# ETH_PCIE_PHY.net
KiCad netlist of a schematic drawn in Altium Designer
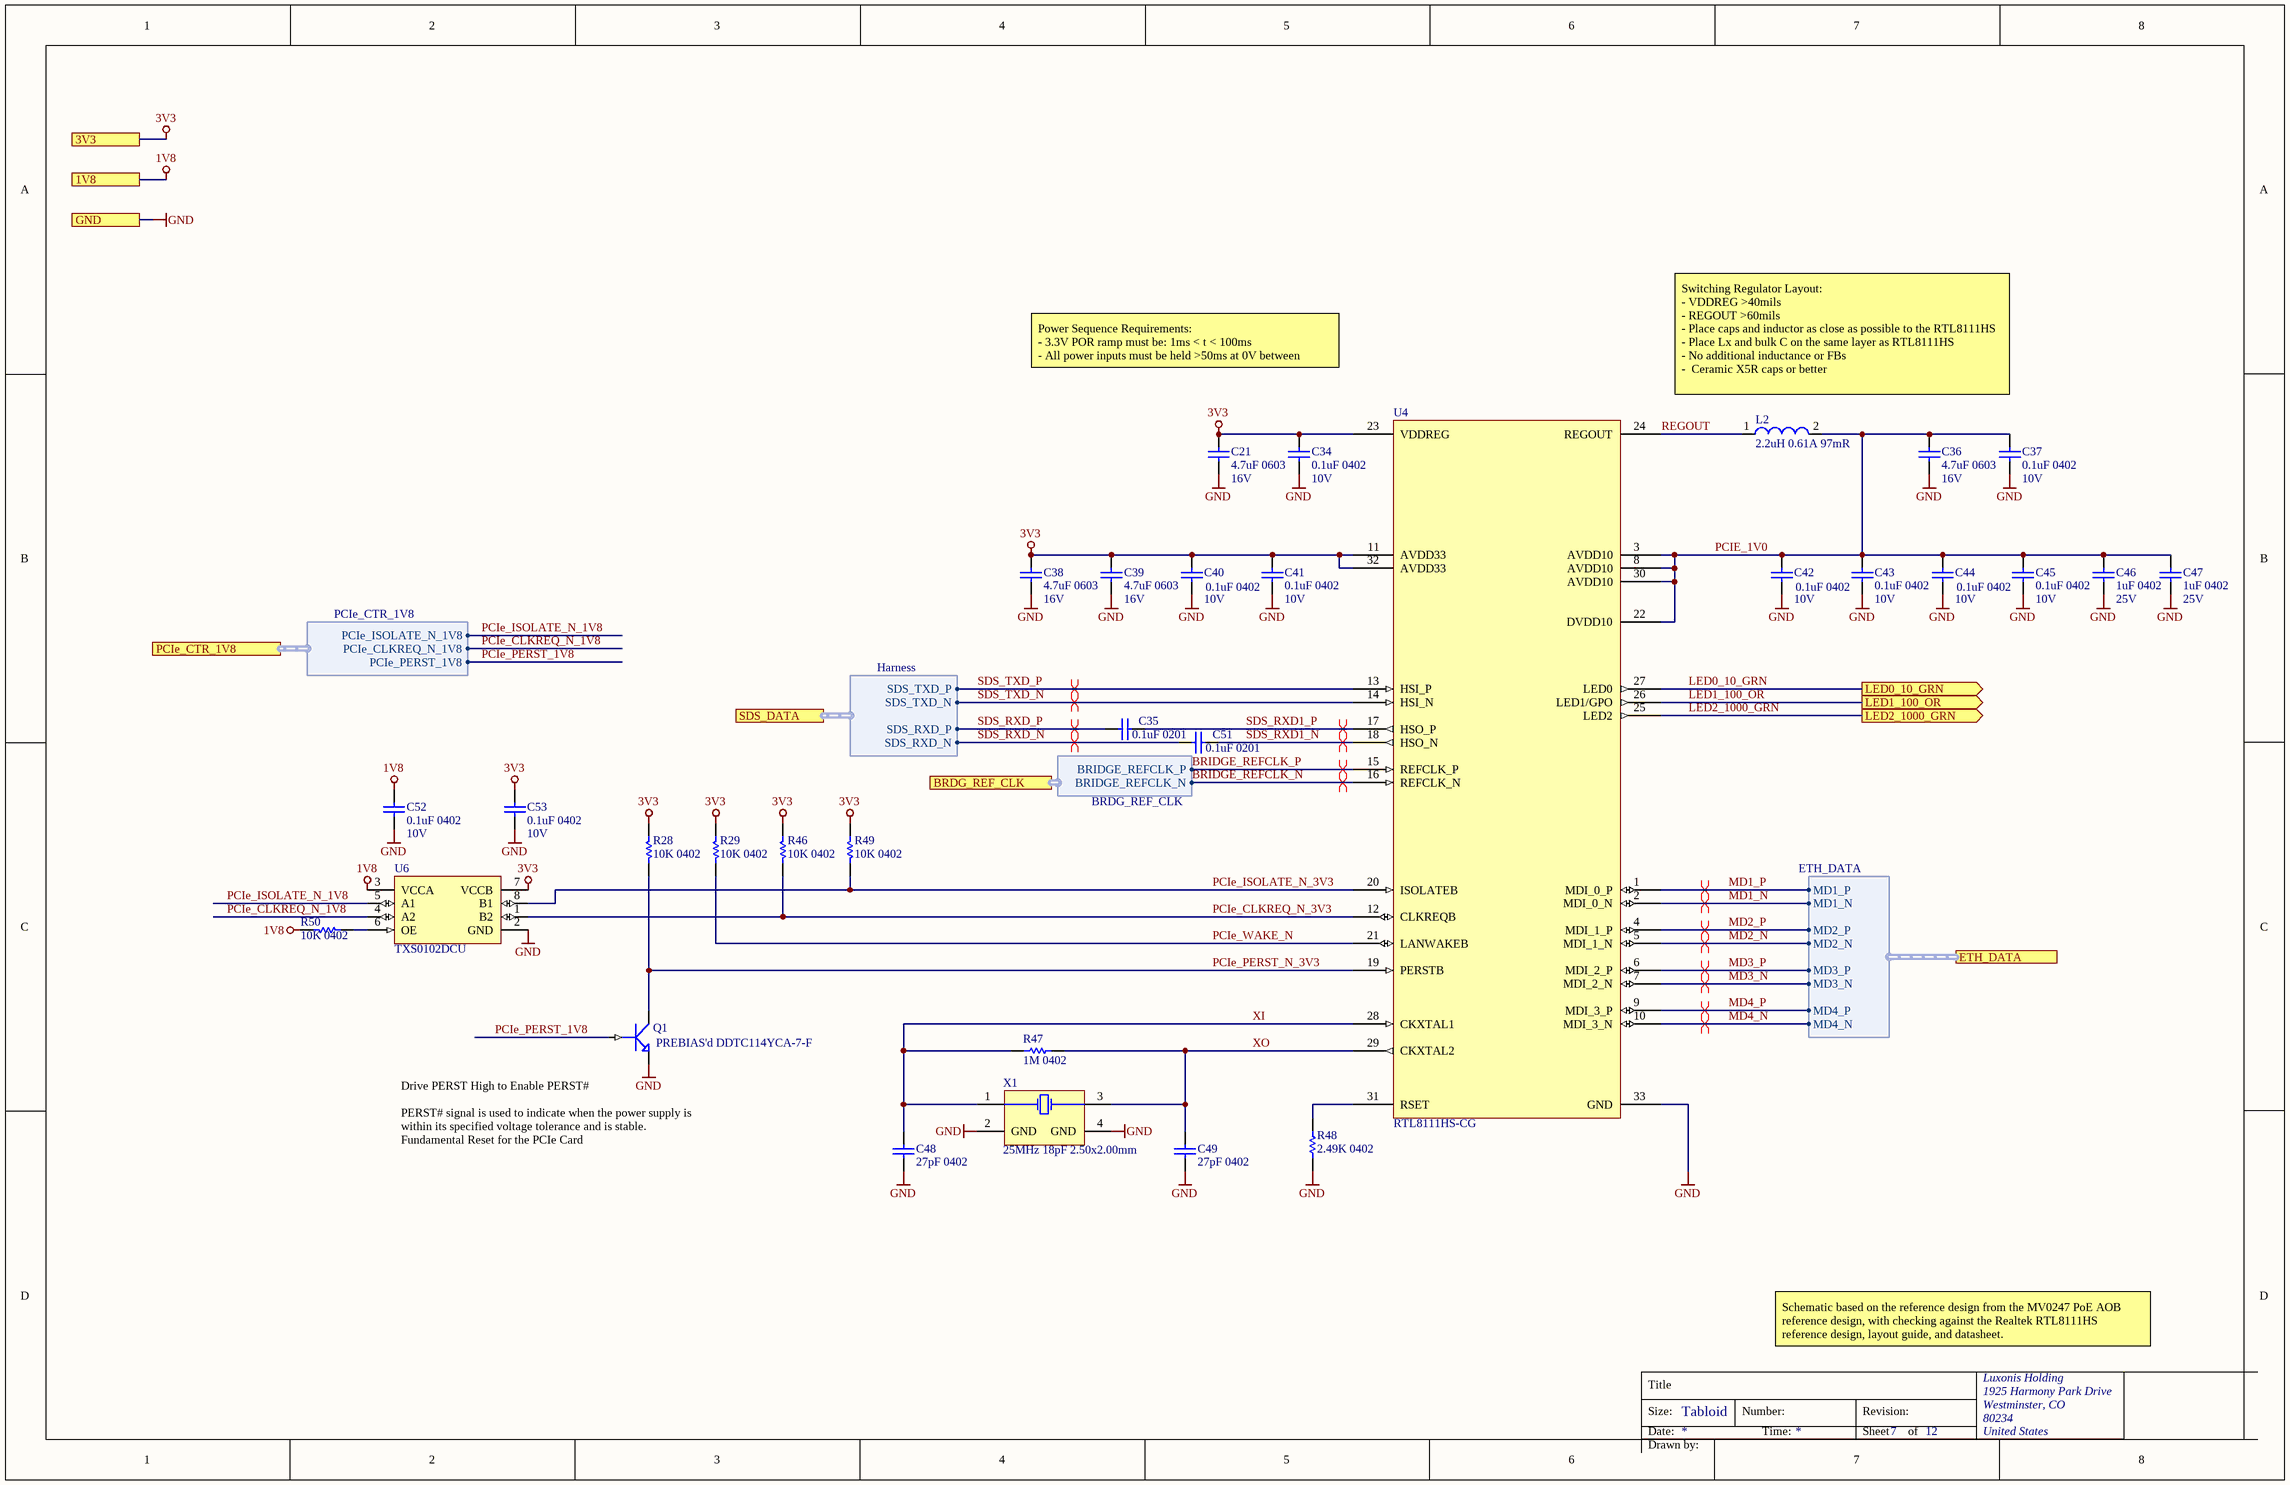
[diagram p0: ETH_PCIE_PHY.SchDoc]

(export (version "E")
  (design (tool "Eeschema 10.0.6"))
  (components
    (comp (ref "C21")
      (value "4.7uF 0603")
      (footprint "CAP_Altium_Vault_Generic:CAPC0603(1608)100_N")
      (description "CAP CER 4.7UF 16V X5R 0603 10%")
      (fields (field (name "TOLERANCE") "10%") (field (name "VOLTAGE RATING") "16V"))
      (libsource (lib "LuxonisMaster") (part "GRM188R61C475KAAJD"))
    )
    (comp (ref "C34")
      (value "0.1uF 0402")
      (footprint "CAP_Altium_Vault_Generic:CAPC0402(1005)70_N")
      (description "CAP CER 0.1UF 10V X7R 0402 5%")
      (fields (field (name "TOLERANCE") "5%") (field (name "VOLTAGE RATING") "10V"))
      (libsource (lib "LuxonisMaster") (part "GRM155R71A104JA01D"))
    )
    (comp (ref "C35")
      (value "0.1uF 0201")
      (footprint "CAP_Altium_Vault_Generic:CAPC0201(0603)33_L")
      (description "CAP CER 0.1UF 10V X5R 0201")
      (fields (field (name "TOLERANCE") "10%") (field (name "VOLTAGE") "10V"))
      (libsource (lib "LuxonisMaster") (part "GRM033R61A104KE15D"))
    )
    (comp (ref "C36")
      (value "4.7uF 0603")
      (footprint "CAP_Altium_Vault_Generic:CAPC0603(1608)100_N")
      (description "CAP CER 4.7UF 16V X5R 0603 10%")
      (fields (field (name "TOLERANCE") "10%") (field (name "VOLTAGE RATING") "16V"))
      (libsource (lib "LuxonisMaster") (part "GRM188R61C475KAAJD"))
    )
    (comp (ref "C37")
      (value "0.1uF 0402")
      (footprint "CAP_Altium_Vault_Generic:CAPC0402(1005)70_N")
      (description "CAP CER 0.1UF 10V X7R 0402 5%")
      (fields (field (name "TOLERANCE") "5%") (field (name "VOLTAGE RATING") "10V"))
      (libsource (lib "LuxonisMaster") (part "GRM155R71A104JA01D"))
    )
    (comp (ref "C38")
      (value "4.7uF 0603")
      (footprint "CAP_Altium_Vault_Generic:CAPC0603(1608)100_N")
      (description "CAP CER 4.7UF 16V X5R 0603 10%")
      (fields (field (name "TOLERANCE") "10%") (field (name "VOLTAGE RATING") "16V"))
      (libsource (lib "LuxonisMaster") (part "GRM188R61C475KAAJD"))
    )
    (comp (ref "C39")
      (value "4.7uF 0603")
      (footprint "CAP_Altium_Vault_Generic:CAPC0603(1608)100_N")
      (description "CAP CER 4.7UF 16V X5R 0603 10%")
      (fields (field (name "TOLERANCE") "10%") (field (name "VOLTAGE RATING") "16V"))
      (libsource (lib "LuxonisMaster") (part "GRM188R61C475KAAJD"))
    )
    (comp (ref "C40")
      (value "0.1uF 0402")
      (footprint "CAP_Altium_Vault_Generic:CAPC0402(1005)70_N")
      (description "CAP CER 0.1UF 10V X7R 0402 5%")
      (fields (field (name "TOLERANCE") "5%") (field (name "VOLTAGE RATING") "10V"))
      (libsource (lib "LuxonisMaster") (part "GRM155R71A104JA01D"))
    )
    (comp (ref "C41")
      (value "0.1uF 0402")
      (footprint "CAP_Altium_Vault_Generic:CAPC0402(1005)70_N")
      (description "CAP CER 0.1UF 10V X7R 0402 5%")
      (fields (field (name "TOLERANCE") "5%") (field (name "VOLTAGE RATING") "10V"))
      (libsource (lib "LuxonisMaster") (part "GRM155R71A104JA01D"))
    )
    (comp (ref "C42")
      (value "0.1uF 0402")
      (footprint "CAP_Altium_Vault_Generic:CAPC0402(1005)70_N")
      (description "CAP CER 0.1UF 10V X7R 0402 5%")
      (fields (field (name "TOLERANCE") "5%") (field (name "VOLTAGE RATING") "10V"))
      (libsource (lib "LuxonisMaster") (part "GRM155R71A104JA01D"))
    )
    (comp (ref "C43")
      (value "0.1uF 0402")
      (footprint "CAP_Altium_Vault_Generic:CAPC0402(1005)70_N")
      (description "CAP CER 0.1UF 10V X7R 0402 5%")
      (fields (field (name "TOLERANCE") "5%") (field (name "VOLTAGE RATING") "10V"))
      (libsource (lib "LuxonisMaster") (part "GRM155R71A104JA01D"))
    )
    (comp (ref "C44")
      (value "0.1uF 0402")
      (footprint "CAP_Altium_Vault_Generic:CAPC0402(1005)70_N")
      (description "CAP CER 0.1UF 10V X7R 0402 5%")
      (fields (field (name "TOLERANCE") "5%") (field (name "VOLTAGE RATING") "10V"))
      (libsource (lib "LuxonisMaster") (part "GRM155R71A104JA01D"))
    )
    (comp (ref "C45")
      (value "0.1uF 0402")
      (footprint "CAP_Altium_Vault_Generic:CAPC0402(1005)70_N")
      (description "CAP CER 0.1UF 10V X7R 0402 5%")
      (fields (field (name "TOLERANCE") "5%") (field (name "VOLTAGE RATING") "10V"))
      (libsource (lib "LuxonisMaster") (part "GRM155R71A104JA01D"))
    )
    (comp (ref "C46")
      (value "1uF 0402")
      (footprint "CAP_Altium_Vault_Generic:CAPC0402(1005)70_N")
      (description "CAP CER 1UF 25V X5R 0402 10%")
      (fields
        (field (name "TOLERANCE") "10%")
        (field (name "VOLTAGE") "25V")
        (field (name "VOLTAGE RATING") "25V")
      )
      (libsource (lib "LuxonisMaster") (part "GRM155R61E105KA12D"))
    )
    (comp (ref "C47")
      (value "1uF 0402")
      (footprint "CAP_Altium_Vault_Generic:CAPC0402(1005)70_N")
      (description "CAP CER 1UF 25V X5R 0402 10%")
      (fields
        (field (name "TOLERANCE") "10%")
        (field (name "VOLTAGE") "25V")
        (field (name "VOLTAGE RATING") "25V")
      )
      (libsource (lib "LuxonisMaster") (part "GRM155R61E105KA12D"))
    )
    (comp (ref "C48")
      (value "27pF 0402")
      (footprint "CAP_Altium_Vault_Generic:CAPC0402(1005)60_N")
      (description "CAP CER 27PF 50V C0G/NP0 0402")
      (fields (field (name "TOLERANCE") "5%") (field (name "VOLTAGE") "50V"))
      (libsource (lib "BW2098POE") (part "C0402C270J5GACTU"))
    )
    (comp (ref "C49")
      (value "27pF 0402")
      (footprint "CAP_Altium_Vault_Generic:CAPC0402(1005)60_N")
      (description "CAP CER 27PF 50V C0G/NP0 0402")
      (fields (field (name "TOLERANCE") "5%") (field (name "VOLTAGE") "50V"))
      (libsource (lib "BW2098POE") (part "C0402C270J5GACTU"))
    )
    (comp (ref "C51")
      (value "0.1uF 0201")
      (footprint "CAP_Altium_Vault_Generic:CAPC0201(0603)33_L")
      (description "CAP CER 0.1UF 10V X5R 0201")
      (fields (field (name "TOLERANCE") "10%") (field (name "VOLTAGE") "10V"))
      (libsource (lib "LuxonisMaster") (part "GRM033R61A104KE15D"))
    )
    (comp (ref "C52")
      (value "0.1uF 0402")
      (footprint "CAP_Altium_Vault_Generic:CAPC0402(1005)70_N")
      (description "CAP CER 0.1UF 10V X7R 0402 5%")
      (fields (field (name "TOLERANCE") "5%") (field (name "VOLTAGE RATING") "10V"))
      (libsource (lib "LuxonisMaster") (part "GRM155R71A104JA01D"))
    )
    (comp (ref "C53")
      (value "0.1uF 0402")
      (footprint "CAP_Altium_Vault_Generic:CAPC0402(1005)70_N")
      (description "CAP CER 0.1UF 10V X7R 0402 5%")
      (fields (field (name "TOLERANCE") "5%") (field (name "VOLTAGE RATING") "10V"))
      (libsource (lib "LuxonisMaster") (part "GRM155R71A104JA01D"))
    )
    (comp (ref "L2")
      (value "2.2uH 0.61A 97mR")
      (footprint "BW2098POE:LQH32NH2R2J23L")
      (description "FIXED IND 2.2UH 610MA 97MOHM SMD")
      (fields (field (name "TOLERANCE") "5%"))
      (libsource (lib "BW2098POE") (part "LQH32NH2R2J23L"))
    )
    (comp (ref "Q1")
      (value "PREBIAS'd DDTC114YCA-7-F")
      (footprint "BW2098POE:DDTC114YCA-7-F")
      (description "TRANS PREBIAS NPN 200MW SOT23-3")
      (libsource (lib "BW2098POE") (part "DDTC114YCA-7-F"))
    )
    (comp (ref "R28")
      (value "10K 0402")
      (footprint "RES_Altium_Vault_Generic:RESC0402(1005)_N")
      (fields (field (name "TOLERANCE") "1%"))
      (libsource (lib "LuxonisMaster") (part "RC0402FR-1310KL"))
    )
    (comp (ref "R29")
      (value "10K 0402")
      (footprint "RES_Altium_Vault_Generic:RESC0402(1005)_N")
      (fields (field (name "TOLERANCE") "1%"))
      (libsource (lib "LuxonisMaster") (part "RC0402FR-1310KL"))
    )
    (comp (ref "R46")
      (value "10K 0402")
      (footprint "RES_Altium_Vault_Generic:RESC0402(1005)_N")
      (fields (field (name "TOLERANCE") "1%"))
      (libsource (lib "LuxonisMaster") (part "RC0402FR-1310KL"))
    )
    (comp (ref "R47")
      (value "1M 0402")
      (footprint "RES_Altium_Vault_Generic:RESC0402(1005)_N")
      (description "RES SMD 1M OHM 1% 1/16W 0402")
      (fields (field (name "TOLERANCE") "1%"))
      (libsource (lib "LuxonisMaster") (part "RC0402FR-071ML"))
    )
    (comp (ref "R48")
      (value "2.49K 0402")
      (footprint "RES_Altium_Vault_Generic:RESC0402(1005)_N")
      (description "RES SMD 2.49K OHM 1% 1/16W 0402")
      (fields (field (name "TOLERANCE") "1%"))
      (libsource (lib "BW2098POE") (part "RC0402FR-072K49L"))
    )
    (comp (ref "R49")
      (value "10K 0402")
      (footprint "RES_Altium_Vault_Generic:RESC0402(1005)_N")
      (fields (field (name "TOLERANCE") "1%"))
      (libsource (lib "LuxonisMaster") (part "RC0402FR-1310KL"))
    )
    (comp (ref "R50")
      (value "10K 0402")
      (footprint "RES_Altium_Vault_Generic:RESC0402(1005)_N")
      (fields (field (name "TOLERANCE") "1%"))
      (libsource (lib "LuxonisMaster") (part "RC0402FR-1310KL"))
    )
    (comp (ref "U4")
      (value "RTL8111HS-CG")
      (footprint "BW2098POE:RTL8111Hx-CG")
      (description "IC ETHERNET/PCIe PHY Realtek")
      (libsource (lib "BW2098POE") (part "RTL8111HS"))
    )
    (comp (ref "U6")
      (value "TXS0102DCU")
      (footprint "BW2098POE:TXS0102DCUR")
      (description "TEXAS INSTRUMENTS - TXS0102DCUR - IC, TRANSLATOR, 2 BIT, BI, US-8")
      (libsource (lib "BW2098POE") (part "TXS0102DCUR"))
    )
    (comp (ref "X1")
      (value "25MHz 18pF 2.50x2.00mm")
      (footprint "BW2098POE:ECS-250-18-36B-CKY-TR")
      (description "CRYSTAL 25.0000MHZ 18PF SMD 25MHz ±10ppm Crystal 18pF 50 Ohms 4-SMD, No Lead")
      (libsource (lib "BW2098POE") (part "ECS-250-18-36B-CKY-TR"))
    )
  )
  (nets
    (net (code "5") (name "/BRIDGE_REFCLK_N") (class "Default")
      (node (ref "U4") (pin "16") (pinfunction "REFCLK_N_16") (pintype "input"))
    )
    (net (code "6") (name "/BRIDGE_REFCLK_P") (class "Default")
      (node (ref "U4") (pin "15") (pinfunction "REFCLK_P_15") (pintype "input"))
    )
    (net (code "7") (name "/LED0_10_GRN") (class "Default")
      (node (ref "U4") (pin "27") (pinfunction "LED0_27") (pintype "output"))
    )
    (net (code "8") (name "/LED1_100_OR") (class "Default")
      (node (ref "U4") (pin "26") (pinfunction "LED1/GPO_26") (pintype "output"))
    )
    (net (code "9") (name "/LED2_1000_GRN") (class "Default")
      (node (ref "U4") (pin "25") (pinfunction "LED2_25") (pintype "output"))
    )
    (net (code "10") (name "/MD1_N") (class "Default")
      (node (ref "U4") (pin "2") (pinfunction "MDI_0_N_2") (pintype "bidirectional"))
    )
    (net (code "11") (name "/MD1_P") (class "Default")
      (node (ref "U4") (pin "1") (pinfunction "MDI_0_P_1") (pintype "bidirectional"))
    )
    (net (code "12") (name "/MD2_N") (class "Default")
      (node (ref "U4") (pin "5") (pinfunction "MDI_1_N_5") (pintype "bidirectional"))
    )
    (net (code "13") (name "/MD2_P") (class "Default")
      (node (ref "U4") (pin "4") (pinfunction "MDI_1_P_4") (pintype "bidirectional"))
    )
    (net (code "14") (name "/MD3_N") (class "Default")
      (node (ref "U4") (pin "7") (pinfunction "MDI_2_N_7") (pintype "bidirectional"))
    )
    (net (code "15") (name "/MD3_P") (class "Default")
      (node (ref "U4") (pin "6") (pinfunction "MDI_2_P_6") (pintype "bidirectional"))
    )
    (net (code "16") (name "/MD4_N") (class "Default")
      (node (ref "U4") (pin "10") (pinfunction "MDI_3_N_10") (pintype "bidirectional"))
    )
    (net (code "17") (name "/MD4_P") (class "Default")
      (node (ref "U4") (pin "9") (pinfunction "MDI_3_P_9") (pintype "bidirectional"))
    )
    (net (code "18") (name "/PCIE_1V0") (class "Default")
      (node (ref "C36") (pin "2") (pinfunction "2_2") (pintype "passive"))
      (node (ref "C37") (pin "2") (pinfunction "2_2") (pintype "passive"))
      (node (ref "C42") (pin "2") (pinfunction "2_2") (pintype "passive"))
      (node (ref "C43") (pin "2") (pinfunction "2_2") (pintype "passive"))
      (node (ref "C44") (pin "2") (pinfunction "2_2") (pintype "passive"))
      (node (ref "C45") (pin "2") (pinfunction "2_2") (pintype "passive"))
      (node (ref "C46") (pin "2") (pinfunction "2_2") (pintype "passive"))
      (node (ref "C47") (pin "2") (pinfunction "2_2") (pintype "passive"))
      (node (ref "L2") (pin "2") (pinfunction "2_2") (pintype "passive"))
      (node (ref "U4") (pin "22") (pinfunction "DVDD10_22") (pintype "passive"))
      (node (ref "U4") (pin "3") (pinfunction "AVDD10_3") (pintype "passive"))
      (node (ref "U4") (pin "30") (pinfunction "AVDD10_30") (pintype "passive"))
      (node (ref "U4") (pin "8") (pinfunction "AVDD10_8") (pintype "passive"))
    )
    (net (code "19") (name "/PCIe_CLKREQ_N_1V8") (class "Default")
      (node (ref "U6") (pin "4") (pinfunction "A2_4") (pintype "bidirectional"))
    )
    (net (code "20") (name "/PCIe_CLKREQ_N_3V3") (class "Default")
      (node (ref "R46") (pin "2") (pinfunction "2_2") (pintype "passive"))
      (node (ref "U4") (pin "12") (pinfunction "CLKREQB_12") (pintype "bidirectional"))
      (node (ref "U6") (pin "1") (pinfunction "B2_1") (pintype "bidirectional"))
    )
    (net (code "21") (name "/PCIe_ISOLATE_N_1V8") (class "Default")
      (node (ref "U6") (pin "5") (pinfunction "A1_5") (pintype "bidirectional"))
    )
    (net (code "22") (name "/PCIe_ISOLATE_N_3V3") (class "Default")
      (node (ref "R49") (pin "2") (pinfunction "2_2") (pintype "passive"))
      (node (ref "U4") (pin "20") (pinfunction "ISOLATEB_20") (pintype "input"))
      (node (ref "U6") (pin "8") (pinfunction "B1_8") (pintype "bidirectional"))
    )
    (net (code "23") (name "/PCIe_PERST_1V8") (class "Default")
      (node (ref "Q1") (pin "1") (pinfunction "B_1") (pintype "input"))
    )
    (net (code "24") (name "/PCIe_PERST_N_3V3") (class "Default")
      (node (ref "Q1") (pin "3") (pinfunction "C_3") (pintype "passive"))
      (node (ref "R28") (pin "2") (pinfunction "2_2") (pintype "passive"))
      (node (ref "U4") (pin "19") (pinfunction "PERSTB_19") (pintype "input"))
    )
    (net (code "25") (name "/PCIe_WAKE_N") (class "Default")
      (node (ref "R29") (pin "2") (pinfunction "2_2") (pintype "passive"))
      (node (ref "U4") (pin "21") (pinfunction "LANWAKEB_21") (pintype "bidirectional"))
    )
    (net (code "26") (name "/REGOUT") (class "Default")
      (node (ref "L2") (pin "1") (pinfunction "1_1") (pintype "passive"))
      (node (ref "U4") (pin "24") (pinfunction "REGOUT_24") (pintype "passive"))
    )
    (net (code "27") (name "/SDS_RXD1_N") (class "Default")
      (node (ref "C51") (pin "2") (pinfunction "2_2") (pintype "passive"))
      (node (ref "U4") (pin "18") (pinfunction "HSO_N_18") (pintype "output"))
    )
    (net (code "28") (name "/SDS_RXD1_P") (class "Default")
      (node (ref "C35") (pin "2") (pinfunction "2_2") (pintype "passive"))
      (node (ref "U4") (pin "17") (pinfunction "HSO_P_17") (pintype "output"))
    )
    (net (code "29") (name "/SDS_RXD_N") (class "Default")
      (node (ref "C51") (pin "1") (pinfunction "1_1") (pintype "passive"))
    )
    (net (code "30") (name "/SDS_RXD_P") (class "Default")
      (node (ref "C35") (pin "1") (pinfunction "1_1") (pintype "passive"))
    )
    (net (code "31") (name "/SDS_TXD_N") (class "Default")
      (node (ref "U4") (pin "14") (pinfunction "HSI_N_14") (pintype "input"))
    )
    (net (code "32") (name "/SDS_TXD_P") (class "Default")
      (node (ref "U4") (pin "13") (pinfunction "HSI_P_13") (pintype "input"))
    )
    (net (code "33") (name "/XI") (class "Default")
      (node (ref "C48") (pin "2") (pinfunction "2_2") (pintype "passive"))
      (node (ref "R47") (pin "1") (pinfunction "1_1") (pintype "passive"))
      (node (ref "U4") (pin "28") (pinfunction "CKXTAL1_28") (pintype "input"))
      (node (ref "X1") (pin "1") (pinfunction "X1_1") (pintype "passive"))
    )
    (net (code "34") (name "/XO") (class "Default")
      (node (ref "C49") (pin "2") (pinfunction "2_2") (pintype "passive"))
      (node (ref "R47") (pin "2") (pinfunction "2_2") (pintype "passive"))
      (node (ref "U4") (pin "29") (pinfunction "CKXTAL2_29") (pintype "output"))
      (node (ref "X1") (pin "3") (pinfunction "X2_3") (pintype "passive"))
    )
    (net (code "39") (name "1V8") (class "Default")
      (node (ref "C52") (pin "2") (pinfunction "2_2") (pintype "passive"))
      (node (ref "R50") (pin "2") (pinfunction "2_2") (pintype "passive"))
      (node (ref "U6") (pin "3") (pinfunction "VCCA_3") (pintype "power_in"))
    )
    (net (code "40") (name "3V3") (class "Default")
      (node (ref "C21") (pin "2") (pinfunction "2_2") (pintype "passive"))
      (node (ref "C34") (pin "2") (pinfunction "2_2") (pintype "passive"))
      (node (ref "C38") (pin "2") (pinfunction "2_2") (pintype "passive"))
      (node (ref "C39") (pin "2") (pinfunction "2_2") (pintype "passive"))
      (node (ref "C40") (pin "2") (pinfunction "2_2") (pintype "passive"))
      (node (ref "C41") (pin "2") (pinfunction "2_2") (pintype "passive"))
      (node (ref "C53") (pin "2") (pinfunction "2_2") (pintype "passive"))
      (node (ref "R28") (pin "1") (pinfunction "1_1") (pintype "passive"))
      (node (ref "R29") (pin "1") (pinfunction "1_1") (pintype "passive"))
      (node (ref "R46") (pin "1") (pinfunction "1_1") (pintype "passive"))
      (node (ref "R49") (pin "1") (pinfunction "1_1") (pintype "passive"))
      (node (ref "U4") (pin "11") (pinfunction "AVDD33_11") (pintype "passive"))
      (node (ref "U4") (pin "23") (pinfunction "VDDREG_23") (pintype "passive"))
      (node (ref "U4") (pin "32") (pinfunction "AVDD33_32") (pintype "passive"))
      (node (ref "U6") (pin "7") (pinfunction "VCCB_7") (pintype "power_in"))
    )
    (net (code "41") (name "GND") (class "Default")
      (node (ref "C21") (pin "1") (pinfunction "1_1") (pintype "passive"))
      (node (ref "C34") (pin "1") (pinfunction "1_1") (pintype "passive"))
      (node (ref "C36") (pin "1") (pinfunction "1_1") (pintype "passive"))
      (node (ref "C37") (pin "1") (pinfunction "1_1") (pintype "passive"))
      (node (ref "C38") (pin "1") (pinfunction "1_1") (pintype "passive"))
      (node (ref "C39") (pin "1") (pinfunction "1_1") (pintype "passive"))
      (node (ref "C40") (pin "1") (pinfunction "1_1") (pintype "passive"))
      (node (ref "C41") (pin "1") (pinfunction "1_1") (pintype "passive"))
      (node (ref "C42") (pin "1") (pinfunction "1_1") (pintype "passive"))
      (node (ref "C43") (pin "1") (pinfunction "1_1") (pintype "passive"))
      (node (ref "C44") (pin "1") (pinfunction "1_1") (pintype "passive"))
      (node (ref "C45") (pin "1") (pinfunction "1_1") (pintype "passive"))
      (node (ref "C46") (pin "1") (pinfunction "1_1") (pintype "passive"))
      (node (ref "C47") (pin "1") (pinfunction "1_1") (pintype "passive"))
      (node (ref "C48") (pin "1") (pinfunction "1_1") (pintype "passive"))
      (node (ref "C49") (pin "1") (pinfunction "1_1") (pintype "passive"))
      (node (ref "C52") (pin "1") (pinfunction "1_1") (pintype "passive"))
      (node (ref "C53") (pin "1") (pinfunction "1_1") (pintype "passive"))
      (node (ref "Q1") (pin "2") (pinfunction "E_2") (pintype "passive"))
      (node (ref "R48") (pin "1") (pinfunction "1_1") (pintype "passive"))
      (node (ref "U4") (pin "33") (pinfunction "GND_33") (pintype "passive"))
      (node (ref "U6") (pin "2") (pinfunction "GND_2") (pintype "power_in"))
      (node (ref "X1") (pin "2") (pinfunction "GND_2") (pintype "power_in"))
      (node (ref "X1") (pin "4") (pinfunction "GND_4") (pintype "power_in"))
    )
    (net (code "42") (name "Net-(U4-RSET)") (class "Default")
      (node (ref "R48") (pin "2") (pinfunction "2_2") (pintype "passive"))
      (node (ref "U4") (pin "31") (pinfunction "RSET_31") (pintype "passive"))
    )
    (net (code "43") (name "Net-(U6-OE)") (class "Default")
      (node (ref "R50") (pin "1") (pinfunction "1_1") (pintype "passive"))
      (node (ref "U6") (pin "6") (pinfunction "OE_6") (pintype "input"))
    )
  )
)
